# H40R00.net
KiCad netlist of a schematic drawn in EAGLE
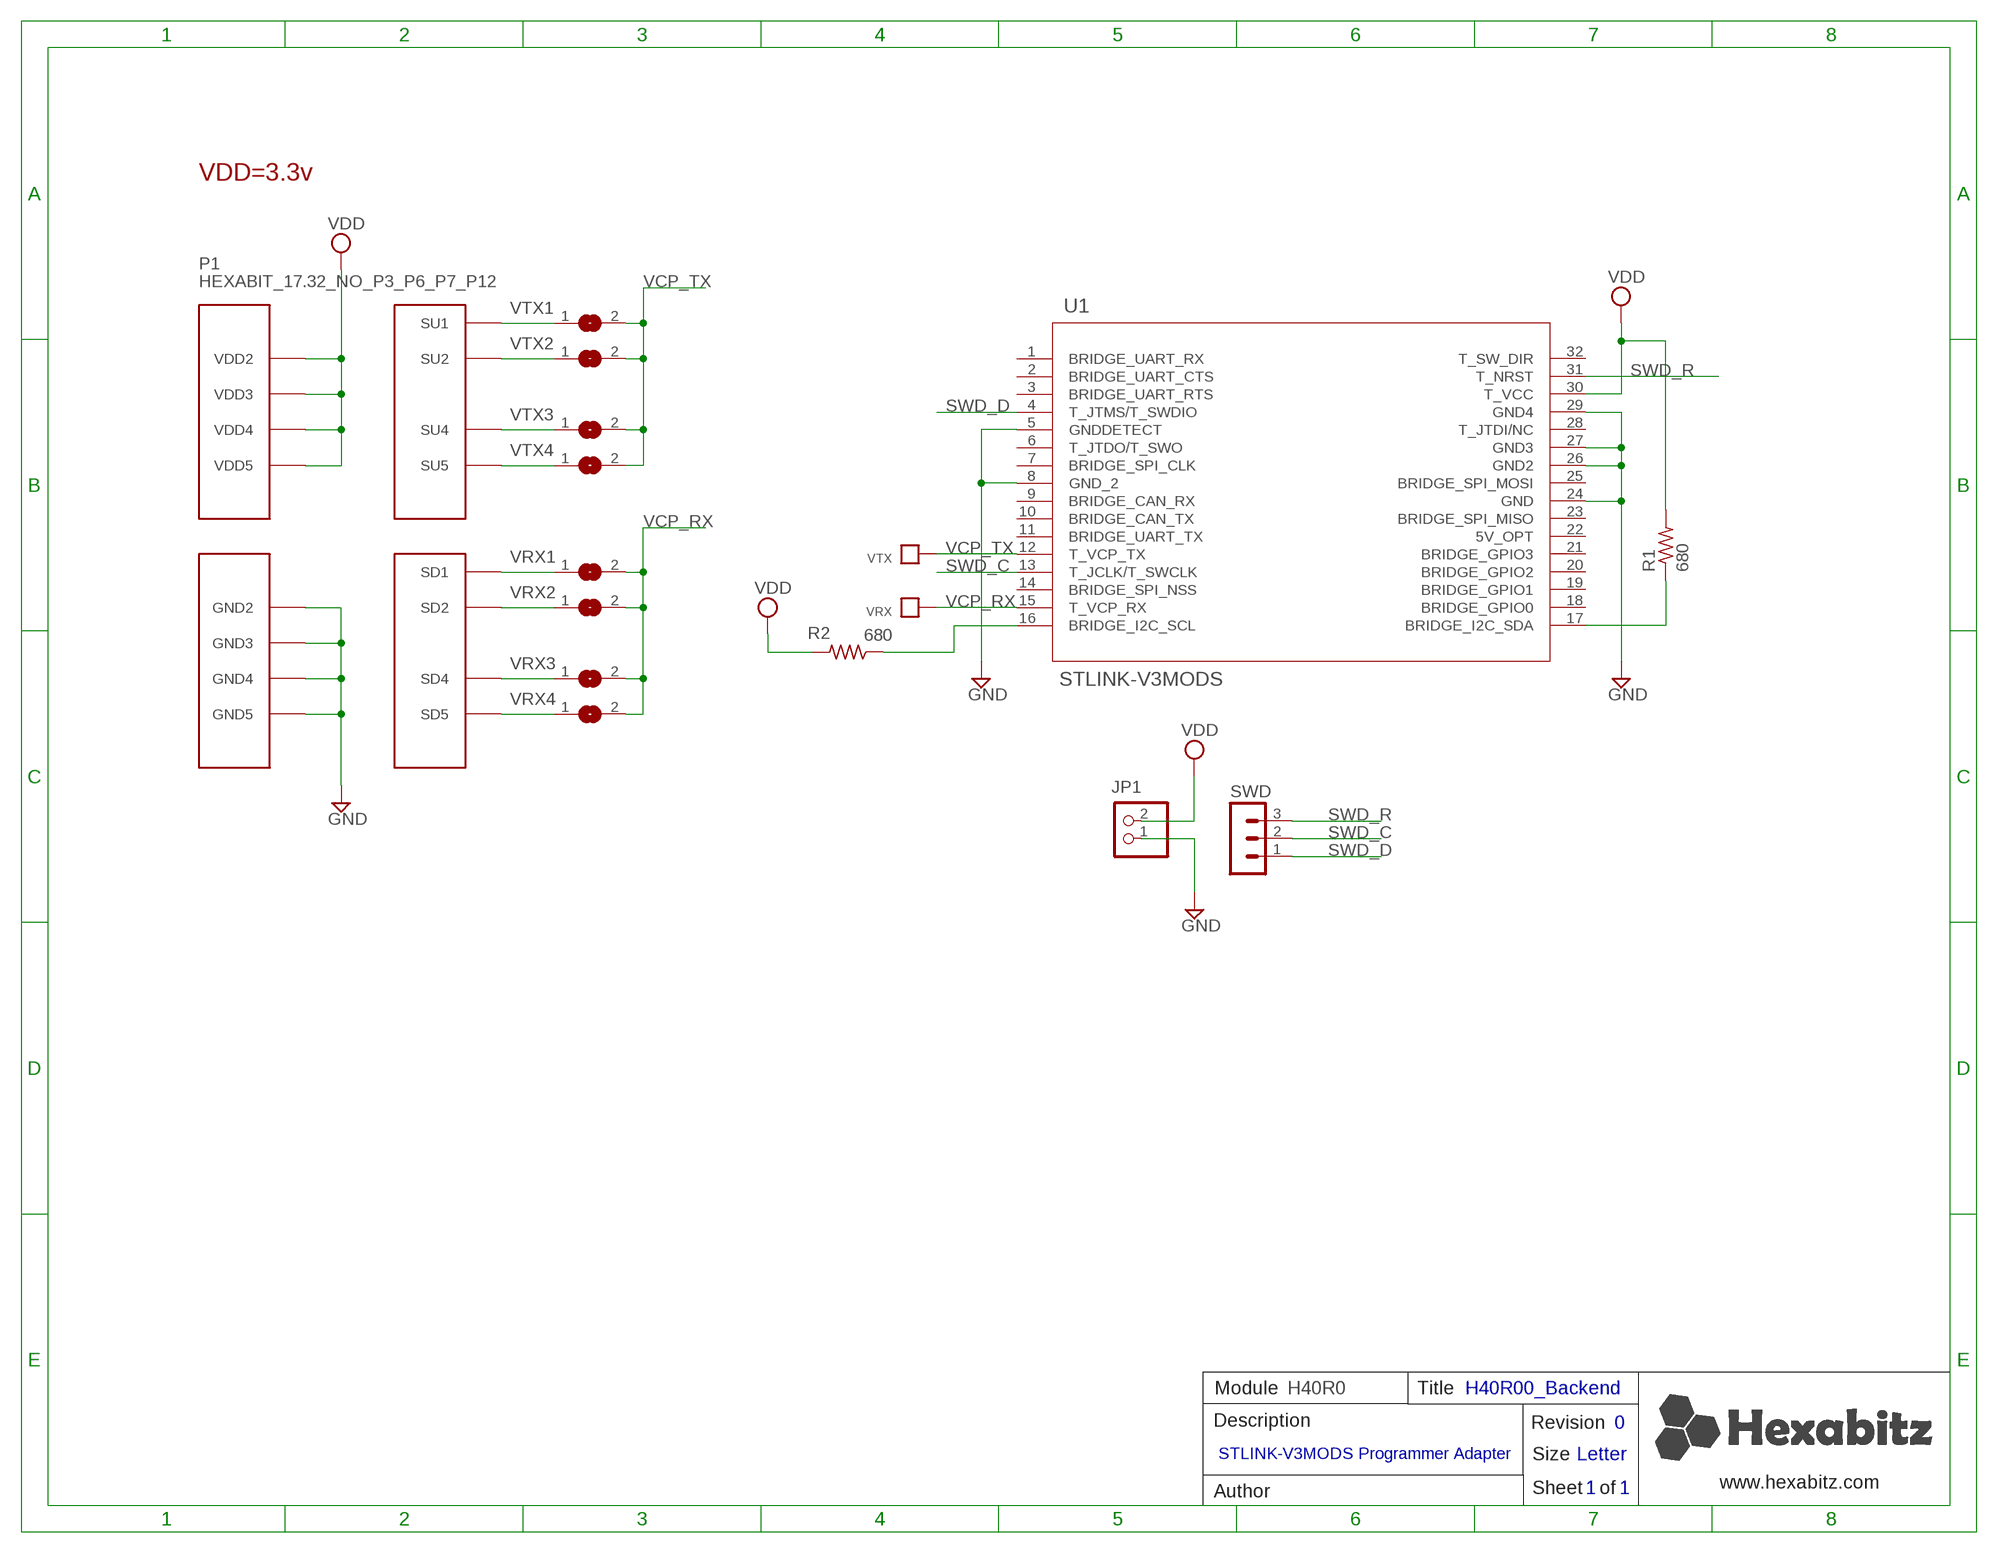
[diagram p0: schematic, sheet 1]

(export (version "E")
  (design (tool "Eeschema 10.0.6"))
  (components
    (comp (ref "JP1")
      (value "PINHD-1X2")
      (footprint "eagle-import:1X02")
      (libsource (lib "eagle-import") (part "PINHD-1X2"))
    )
    (comp (ref "P1")
      (value "HEXABIT_17.32_NO_P3_P6_P7_P12")
      (footprint "eagle-import:HEXABIT_17.32_NO_P3_P6_P7_P12")
      (libsource (lib "eagle-import") (part "HEXABIT_?_NO_P3_P6_P7_P1217.32"))
    )
    (comp (ref "R1")
      (value "680")
      (footprint "eagle-import:R-0603")
      (fields
        (field (name "MFN") "Yageo")
        (field (name "MPN") "RC0603JR-07680RL")
        (field (name "OCTOPART_URL") "https://octopart.com/rc0603jr-07680rl-yageo-40953172?r=sp")
        (field (name "RESISTANCE") "680")
        (field (name "TOLERANCE") "5%")
      )
      (libsource (lib "eagle-import") (part "R-0603"))
    )
    (comp (ref "R2")
      (value "680")
      (footprint "eagle-import:R-0603")
      (fields
        (field (name "MFN") "Yageo")
        (field (name "MPN") "RC0603JR-07680RL")
        (field (name "OCTOPART_URL") "https://octopart.com/rc0603jr-07680rl-yageo-40953172?r=sp")
        (field (name "RESISTANCE") "680")
        (field (name "TOLERANCE") "5%")
      )
      (libsource (lib "eagle-import") (part "R-0603"))
    )
    (comp (ref "SWD")
      (value "MA03-1")
      (footprint "eagle-import:MA03-1")
      (libsource (lib "eagle-import") (part "MA03-1"))
    )
    (comp (ref "U1")
      (value "STLINK-V3MODS")
      (footprint "eagle-import:MOD_STLINK-V3M_MB1467")
      (fields (field (name "MANUFACTURER_PART_NUMBER") "STLINKV3MOS"))
      (libsource (lib "eagle-import") (part "STLINK-V3MODS"))
    )
    (comp (ref "VRX")
      (value "PAD4")
      (footprint "eagle-import:PAD4")
      (libsource (lib "eagle-import") (part "PAD4"))
    )
    (comp (ref "VRX1")
      (value "SJ")
      (footprint "eagle-import:SJ")
      (libsource (lib "eagle-import") (part "SJ"))
    )
    (comp (ref "VRX2")
      (value "SJ")
      (footprint "eagle-import:SJ")
      (libsource (lib "eagle-import") (part "SJ"))
    )
    (comp (ref "VRX3")
      (value "SJ")
      (footprint "eagle-import:SJ")
      (libsource (lib "eagle-import") (part "SJ"))
    )
    (comp (ref "VRX4")
      (value "SJ")
      (footprint "eagle-import:SJ")
      (libsource (lib "eagle-import") (part "SJ"))
    )
    (comp (ref "VTX")
      (value "PAD4")
      (footprint "eagle-import:PAD4")
      (libsource (lib "eagle-import") (part "PAD4"))
    )
    (comp (ref "VTX1")
      (value "SJ")
      (footprint "eagle-import:SJ")
      (libsource (lib "eagle-import") (part "SJ"))
    )
    (comp (ref "VTX2")
      (value "SJ")
      (footprint "eagle-import:SJ")
      (libsource (lib "eagle-import") (part "SJ"))
    )
    (comp (ref "VTX3")
      (value "SJ")
      (footprint "eagle-import:SJ")
      (libsource (lib "eagle-import") (part "SJ"))
    )
    (comp (ref "VTX4")
      (value "SJ")
      (footprint "eagle-import:SJ")
      (libsource (lib "eagle-import") (part "SJ"))
    )
  )
  (nets
    (net (code "1") (name "/SWD_C") (class "Default")
      (node (ref "SWD") (pin "2") (pinfunction "2_2") (pintype "passive"))
      (node (ref "U1") (pin "13") (pinfunction "T_JCLK/T_SWCLK_13") (pintype "passive"))
    )
    (net (code "2") (name "/SWD_D") (class "Default")
      (node (ref "SWD") (pin "1") (pinfunction "1_1") (pintype "passive"))
      (node (ref "U1") (pin "4") (pinfunction "T_JTMS/T_SWDIO_4") (pintype "passive"))
    )
    (net (code "3") (name "/SWD_R") (class "Default")
      (node (ref "SWD") (pin "3") (pinfunction "3_3") (pintype "passive"))
      (node (ref "U1") (pin "31") (pinfunction "T_NRST_31") (pintype "passive"))
    )
    (net (code "4") (name "/VCP_RX") (class "Default")
      (node (ref "U1") (pin "15") (pinfunction "T_VCP_RX_15") (pintype "passive"))
      (node (ref "VRX") (pin "P$1") (pinfunction "P$1_P$1") (pintype "passive"))
      (node (ref "VRX1") (pin "2") (pinfunction "2_2") (pintype "passive"))
      (node (ref "VRX2") (pin "2") (pinfunction "2_2") (pintype "passive"))
      (node (ref "VRX3") (pin "2") (pinfunction "2_2") (pintype "passive"))
      (node (ref "VRX4") (pin "2") (pinfunction "2_2") (pintype "passive"))
    )
    (net (code "5") (name "/VCP_TX") (class "Default")
      (node (ref "U1") (pin "12") (pinfunction "T_VCP_TX_12") (pintype "passive"))
      (node (ref "VTX") (pin "P$1") (pinfunction "P$1_P$1") (pintype "passive"))
      (node (ref "VTX1") (pin "2") (pinfunction "2_2") (pintype "passive"))
      (node (ref "VTX2") (pin "2") (pinfunction "2_2") (pintype "passive"))
      (node (ref "VTX3") (pin "2") (pinfunction "2_2") (pintype "passive"))
      (node (ref "VTX4") (pin "2") (pinfunction "2_2") (pintype "passive"))
    )
    (net (code "6") (name "GND") (class "Default")
      (node (ref "JP1") (pin "1") (pinfunction "1_1") (pintype "passive"))
      (node (ref "P1") (pin "PAD_PD10") (pinfunction "GND4_PAD_PD10") (pintype "power_in"))
      (node (ref "P1") (pin "PAD_PD11") (pinfunction "GND5_PAD_PD11") (pintype "power_in"))
      (node (ref "P1") (pin "PAD_PD8") (pinfunction "GND2_PAD_PD8") (pintype "power_in"))
      (node (ref "P1") (pin "PAD_PD9") (pinfunction "GND3_PAD_PD9") (pintype "power_in"))
      (node (ref "U1") (pin "24") (pinfunction "GND_24") (pintype "passive"))
      (node (ref "U1") (pin "26") (pinfunction "GND2_26") (pintype "passive"))
      (node (ref "U1") (pin "27") (pinfunction "GND3_27") (pintype "passive"))
      (node (ref "U1") (pin "29") (pinfunction "GND4_29") (pintype "passive"))
      (node (ref "U1") (pin "5") (pinfunction "GNDDETECT_5") (pintype "passive"))
      (node (ref "U1") (pin "8") (pinfunction "GND_2_8") (pintype "passive"))
    )
    (net (code "7") (name "Net-(P1-SD1)") (class "Default")
      (node (ref "P1") (pin "PAD_PD1") (pinfunction "SD1_PAD_PD1") (pintype "bidirectional"))
      (node (ref "VRX1") (pin "1") (pinfunction "1_1") (pintype "passive"))
    )
    (net (code "8") (name "Net-(P1-SD2)") (class "Default")
      (node (ref "P1") (pin "PAD_PD2") (pinfunction "SD2_PAD_PD2") (pintype "bidirectional"))
      (node (ref "VRX2") (pin "1") (pinfunction "1_1") (pintype "passive"))
    )
    (net (code "9") (name "Net-(P1-SD4)") (class "Default")
      (node (ref "P1") (pin "PAD_PD4") (pinfunction "SD4_PAD_PD4") (pintype "bidirectional"))
      (node (ref "VRX3") (pin "1") (pinfunction "1_1") (pintype "passive"))
    )
    (net (code "10") (name "Net-(P1-SD5)") (class "Default")
      (node (ref "P1") (pin "PAD_PD5") (pinfunction "SD5_PAD_PD5") (pintype "bidirectional"))
      (node (ref "VRX4") (pin "1") (pinfunction "1_1") (pintype "passive"))
    )
    (net (code "11") (name "Net-(P1-SU1)") (class "Default")
      (node (ref "P1") (pin "PAD_PU1") (pinfunction "SU1_PAD_PU1") (pintype "bidirectional"))
      (node (ref "VTX1") (pin "1") (pinfunction "1_1") (pintype "passive"))
    )
    (net (code "12") (name "Net-(P1-SU2)") (class "Default")
      (node (ref "P1") (pin "PAD_PU2") (pinfunction "SU2_PAD_PU2") (pintype "bidirectional"))
      (node (ref "VTX2") (pin "1") (pinfunction "1_1") (pintype "passive"))
    )
    (net (code "13") (name "Net-(P1-SU4)") (class "Default")
      (node (ref "P1") (pin "PAD_PU4") (pinfunction "SU4_PAD_PU4") (pintype "bidirectional"))
      (node (ref "VTX3") (pin "1") (pinfunction "1_1") (pintype "passive"))
    )
    (net (code "14") (name "Net-(P1-SU5)") (class "Default")
      (node (ref "P1") (pin "PAD_PU5") (pinfunction "SU5_PAD_PU5") (pintype "bidirectional"))
      (node (ref "VTX4") (pin "1") (pinfunction "1_1") (pintype "passive"))
    )
    (net (code "15") (name "Net-(U1-BRIDGE_I2C_SCL)") (class "Default")
      (node (ref "R2") (pin "1") (pinfunction "1_1") (pintype "passive"))
      (node (ref "U1") (pin "16") (pinfunction "BRIDGE_I2C_SCL_16") (pintype "bidirectional"))
    )
    (net (code "16") (name "Net-(U1-BRIDGE_I2C_SDA)") (class "Default")
      (node (ref "R1") (pin "1") (pinfunction "1_1") (pintype "passive"))
      (node (ref "U1") (pin "17") (pinfunction "BRIDGE_I2C_SDA_17") (pintype "bidirectional"))
    )
    (net (code "17") (name "VDD") (class "Default")
      (node (ref "JP1") (pin "2") (pinfunction "2_2") (pintype "passive"))
      (node (ref "P1") (pin "PAD_PU10") (pinfunction "VDD4_PAD_PU10") (pintype "power_in"))
      (node (ref "P1") (pin "PAD_PU11") (pinfunction "VDD5_PAD_PU11") (pintype "power_in"))
      (node (ref "P1") (pin "PAD_PU8") (pinfunction "VDD2_PAD_PU8") (pintype "power_in"))
      (node (ref "P1") (pin "PAD_PU9") (pinfunction "VDD3_PAD_PU9") (pintype "power_in"))
      (node (ref "R1") (pin "2") (pinfunction "2_2") (pintype "passive"))
      (node (ref "R2") (pin "2") (pinfunction "2_2") (pintype "passive"))
      (node (ref "U1") (pin "30") (pinfunction "T_VCC_30") (pintype "passive"))
    )
    (net (code "18") (name "unconnected-(U1-5V_OPT-Pad22)") (class "Default")
      (node (ref "U1") (pin "22") (pinfunction "5V_OPT_22") (pintype "passive"))
    )
    (net (code "19") (name "unconnected-(U1-BRIDGE_CAN_RX-Pad9)") (class "Default")
      (node (ref "U1") (pin "9") (pinfunction "BRIDGE_CAN_RX_9") (pintype "passive"))
    )
    (net (code "20") (name "unconnected-(U1-BRIDGE_CAN_TX-Pad10)") (class "Default")
      (node (ref "U1") (pin "10") (pinfunction "BRIDGE_CAN_TX_10") (pintype "passive"))
    )
    (net (code "21") (name "unconnected-(U1-BRIDGE_GPIO0-Pad18)") (class "Default")
      (node (ref "U1") (pin "18") (pinfunction "BRIDGE_GPIO0_18") (pintype "bidirectional"))
    )
    (net (code "22") (name "unconnected-(U1-BRIDGE_GPIO1-Pad19)") (class "Default")
      (node (ref "U1") (pin "19") (pinfunction "BRIDGE_GPIO1_19") (pintype "bidirectional"))
    )
    (net (code "23") (name "unconnected-(U1-BRIDGE_GPIO2-Pad20)") (class "Default")
      (node (ref "U1") (pin "20") (pinfunction "BRIDGE_GPIO2_20") (pintype "bidirectional"))
    )
    (net (code "24") (name "unconnected-(U1-BRIDGE_GPIO3-Pad21)") (class "Default")
      (node (ref "U1") (pin "21") (pinfunction "BRIDGE_GPIO3_21") (pintype "bidirectional"))
    )
    (net (code "25") (name "unconnected-(U1-BRIDGE_SPI_CLK-Pad7)") (class "Default")
      (node (ref "U1") (pin "7") (pinfunction "BRIDGE_SPI_CLK_7") (pintype "passive"))
    )
    (net (code "26") (name "unconnected-(U1-BRIDGE_SPI_MISO-Pad23)") (class "Default")
      (node (ref "U1") (pin "23") (pinfunction "BRIDGE_SPI_MISO_23") (pintype "passive"))
    )
    (net (code "27") (name "unconnected-(U1-BRIDGE_SPI_MOSI-Pad25)") (class "Default")
      (node (ref "U1") (pin "25") (pinfunction "BRIDGE_SPI_MOSI_25") (pintype "passive"))
    )
    (net (code "28") (name "unconnected-(U1-BRIDGE_SPI_NSS-Pad14)") (class "Default")
      (node (ref "U1") (pin "14") (pinfunction "BRIDGE_SPI_NSS_14") (pintype "passive"))
    )
    (net (code "29") (name "unconnected-(U1-BRIDGE_UART_CTS-Pad2)") (class "Default")
      (node (ref "U1") (pin "2") (pinfunction "BRIDGE_UART_CTS_2") (pintype "passive"))
    )
    (net (code "30") (name "unconnected-(U1-BRIDGE_UART_RTS-Pad3)") (class "Default")
      (node (ref "U1") (pin "3") (pinfunction "BRIDGE_UART_RTS_3") (pintype "passive"))
    )
    (net (code "31") (name "unconnected-(U1-BRIDGE_UART_RX-Pad1)") (class "Default")
      (node (ref "U1") (pin "1") (pinfunction "BRIDGE_UART_RX_1") (pintype "passive"))
    )
    (net (code "32") (name "unconnected-(U1-BRIDGE_UART_TX-Pad11)") (class "Default")
      (node (ref "U1") (pin "11") (pinfunction "BRIDGE_UART_TX_11") (pintype "passive"))
    )
    (net (code "33") (name "unconnected-(U1-T_JTDI{slash}NC-Pad28)") (class "Default")
      (node (ref "U1") (pin "28") (pinfunction "T_JTDI/NC_28") (pintype "passive"))
    )
    (net (code "34") (name "unconnected-(U1-T_JTDO{slash}T_SWO-Pad6)") (class "Default")
      (node (ref "U1") (pin "6") (pinfunction "T_JTDO/T_SWO_6") (pintype "passive"))
    )
    (net (code "35") (name "unconnected-(U1-T_SW_DIR-Pad32)") (class "Default")
      (node (ref "U1") (pin "32") (pinfunction "T_SW_DIR_32") (pintype "passive"))
    )
  )
)
